# rapidshark-display-shifter-mk-2_2-fab.net
KiCad netlist of a schematic drawn in EAGLE
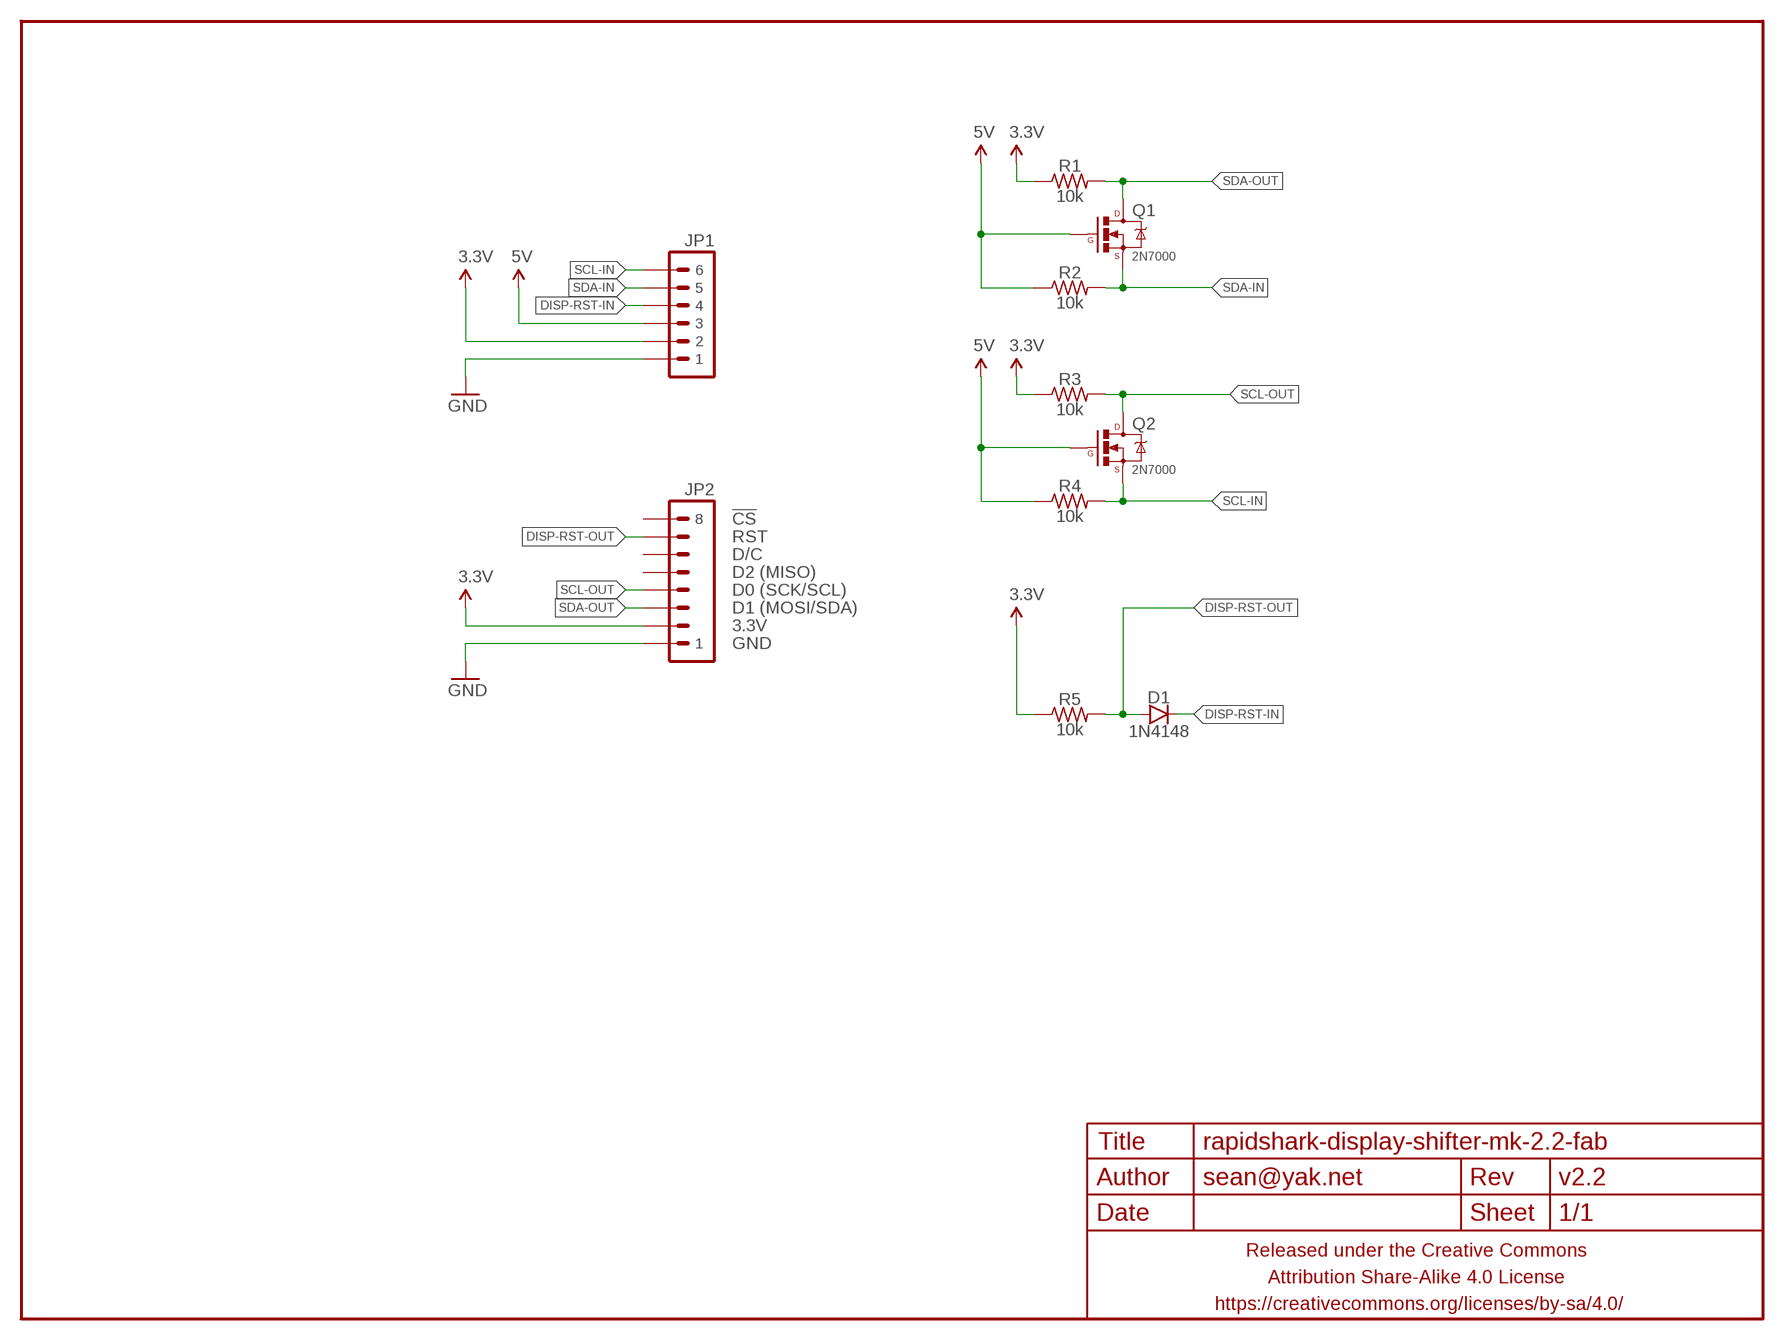
[diagram p0: schematic, sheet 1]

(export (version "E")
  (design (tool "Eeschema 10.0.6"))
  (components
    (comp (ref "D1")
      (value "1N4148")
      (footprint "eagle-import:DIODE-7.62MM")
      (libsource (lib "eagle-import") (part "DIODEPTH-7.62MM"))
    )
    (comp (ref "FRAME1")
      (value "FRAME-LETTERNO_PACKAGE")
      (footprint "eagle-import:DUMMY")
      (fields (field (name "DESIGNER") "sean@yak.net") (field (name "VERSION") "v2.2"))
      (libsource (lib "eagle-import") (part "FRAME-LETTERNO_PACKAGE"))
    )
    (comp (ref "JP1")
      (value "M06JST-PH-PTH-VERT")
      (footprint "eagle-import:JST-6-PH-VERT-PTH")
      (libsource (lib "eagle-import") (part "M06JST-PH-PTH-VERT"))
    )
    (comp (ref "JP2")
      (value "M08PTH-1.2MMHOLES")
      (footprint "eagle-import:1X08-1.2MMHOLES")
      (libsource (lib "eagle-import") (part "M08PTH-1.2MMHOLES"))
    )
    (comp (ref "Q1")
      (value "2N7000")
      (footprint "eagle-import:TO-92-AMMO")
      (libsource (lib "eagle-import") (part "MOSFET-NCHANNEL2N7000-AMMO"))
    )
    (comp (ref "Q2")
      (value "2N7000")
      (footprint "eagle-import:TO-92-AMMO")
      (libsource (lib "eagle-import") (part "MOSFET-NCHANNEL2N7000-AMMO"))
    )
    (comp (ref "R1")
      (value "10k")
      (footprint "eagle-import:RESISTOR-AXIAL-PTH-5.08MM")
      (libsource (lib "eagle-import") (part "RESISTORPTH-AXIAL-5.08MM"))
    )
    (comp (ref "R2")
      (value "10k")
      (footprint "eagle-import:RESISTOR-AXIAL-PTH-5.08MM")
      (libsource (lib "eagle-import") (part "RESISTORPTH-AXIAL-5.08MM"))
    )
    (comp (ref "R3")
      (value "10k")
      (footprint "eagle-import:RESISTOR-AXIAL-PTH-5.08MM")
      (libsource (lib "eagle-import") (part "RESISTORPTH-AXIAL-5.08MM"))
    )
    (comp (ref "R4")
      (value "10k")
      (footprint "eagle-import:RESISTOR-AXIAL-PTH-5.08MM")
      (libsource (lib "eagle-import") (part "RESISTORPTH-AXIAL-5.08MM"))
    )
    (comp (ref "R5")
      (value "10k")
      (footprint "eagle-import:RESISTOR-AXIAL-PTH-5.08MM")
      (libsource (lib "eagle-import") (part "RESISTORPTH-AXIAL-5.08MM"))
    )
  )
  (nets
    (net (code "1") (name "3.3V") (class "Default")
      (node (ref "JP1") (pin "2") (pinfunction "2_2") (pintype "passive"))
      (node (ref "JP2") (pin "2") (pinfunction "2_2") (pintype "passive"))
      (node (ref "R1") (pin "P$1") (pinfunction "1_P$1") (pintype "passive"))
      (node (ref "R3") (pin "P$1") (pinfunction "1_P$1") (pintype "passive"))
      (node (ref "R5") (pin "P$1") (pinfunction "1_P$1") (pintype "passive"))
    )
    (net (code "2") (name "5V") (class "Default")
      (node (ref "JP1") (pin "3") (pinfunction "3_3") (pintype "passive"))
      (node (ref "Q1") (pin "2") (pinfunction "G_2") (pintype "passive"))
      (node (ref "Q2") (pin "2") (pinfunction "G_2") (pintype "passive"))
      (node (ref "R2") (pin "P$1") (pinfunction "1_P$1") (pintype "passive"))
      (node (ref "R4") (pin "P$1") (pinfunction "1_P$1") (pintype "passive"))
    )
    (net (code "3") (name "DISP-RST-IN") (class "Default")
      (node (ref "D1") (pin "K") (pinfunction "C_K") (pintype "passive"))
      (node (ref "JP1") (pin "4") (pinfunction "4_4") (pintype "passive"))
    )
    (net (code "4") (name "DISP-RST-OUT") (class "Default")
      (node (ref "D1") (pin "A") (pinfunction "A_A") (pintype "passive"))
      (node (ref "JP2") (pin "7") (pinfunction "7_7") (pintype "passive"))
      (node (ref "R5") (pin "P$2") (pinfunction "2_P$2") (pintype "passive"))
    )
    (net (code "5") (name "GND") (class "Default")
      (node (ref "JP1") (pin "1") (pinfunction "1_1") (pintype "passive"))
      (node (ref "JP2") (pin "1") (pinfunction "1_1") (pintype "passive"))
    )
    (net (code "6") (name "SCL-IN") (class "Default")
      (node (ref "JP1") (pin "6") (pinfunction "6_6") (pintype "passive"))
      (node (ref "Q2") (pin "1") (pinfunction "S_1") (pintype "passive"))
      (node (ref "R4") (pin "P$2") (pinfunction "2_P$2") (pintype "passive"))
    )
    (net (code "7") (name "SCL-OUT") (class "Default")
      (node (ref "JP2") (pin "4") (pinfunction "4_4") (pintype "passive"))
      (node (ref "Q2") (pin "3") (pinfunction "D_3") (pintype "passive"))
      (node (ref "R3") (pin "P$2") (pinfunction "2_P$2") (pintype "passive"))
    )
    (net (code "8") (name "SDA-IN") (class "Default")
      (node (ref "JP1") (pin "5") (pinfunction "5_5") (pintype "passive"))
      (node (ref "Q1") (pin "1") (pinfunction "S_1") (pintype "passive"))
      (node (ref "R2") (pin "P$2") (pinfunction "2_P$2") (pintype "passive"))
    )
    (net (code "9") (name "SDA-OUT") (class "Default")
      (node (ref "JP2") (pin "3") (pinfunction "3_3") (pintype "passive"))
      (node (ref "Q1") (pin "3") (pinfunction "D_3") (pintype "passive"))
      (node (ref "R1") (pin "P$2") (pinfunction "2_P$2") (pintype "passive"))
    )
    (net (code "10") (name "unconnected-(JP2-Pad5)") (class "Default")
      (node (ref "JP2") (pin "5") (pinfunction "5_5") (pintype "passive"))
    )
    (net (code "11") (name "unconnected-(JP2-Pad6)") (class "Default")
      (node (ref "JP2") (pin "6") (pinfunction "6_6") (pintype "passive"))
    )
    (net (code "12") (name "unconnected-(JP2-Pad8)") (class "Default")
      (node (ref "JP2") (pin "8") (pinfunction "8_8") (pintype "passive"))
    )
  )
)
